# DCDCFinalSchematic.net
KiCad netlist of a schematic drawn in EAGLE
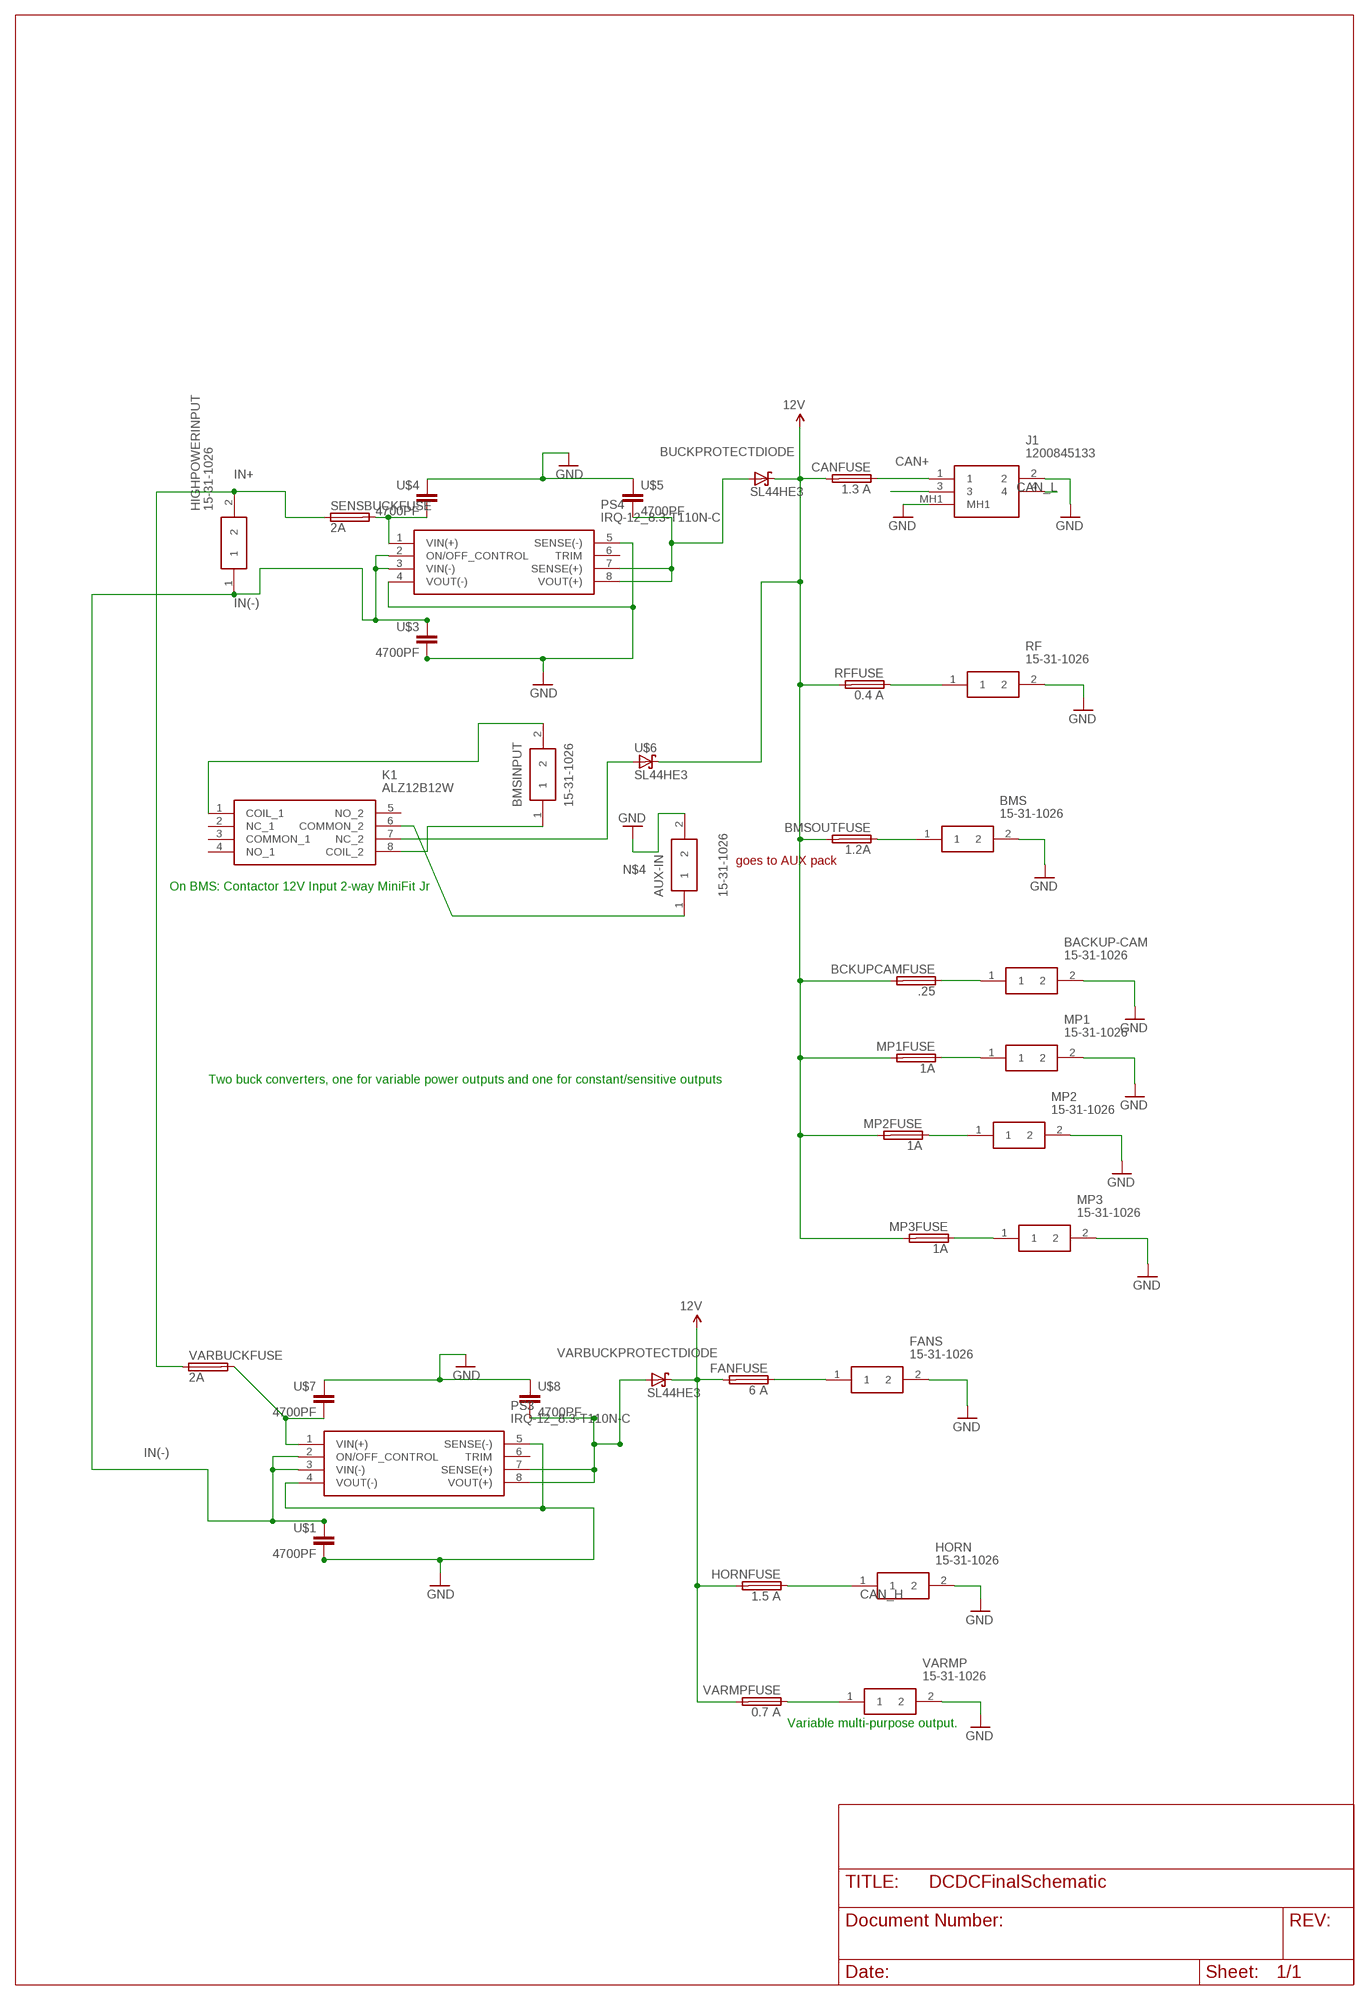
[diagram p0: schematic, sheet 1]

(export (version "E")
  (design (tool "Eeschema 10.0.6"))
  (components
    (comp (ref "AUX-IN")
      (value "15-31-1026")
      (footprint "eagle-import:15311026")
      (fields (field (name "MOUSER_PART_NUMBER") "538-15-31-1026"))
      (libsource (lib "eagle-import") (part "15-31-1026"))
    )
    (comp (ref "BACKUP-CAM")
      (value "15-31-1026")
      (footprint "eagle-import:15311026")
      (fields (field (name "MOUSER_PART_NUMBER") "538-15-31-1026"))
      (libsource (lib "eagle-import") (part "15-31-1026"))
    )
    (comp (ref "BCKUPCAMFUSE")
      (value ".25")
      (footprint "eagle-import:OMNIBLOK")
      (libsource (lib "eagle-import") (part "SMD-MICRO-FUSE-BLOCK"))
    )
    (comp (ref "BMS")
      (value "15-31-1026")
      (footprint "eagle-import:15311026")
      (fields (field (name "MOUSER_PART_NUMBER") "538-15-31-1026"))
      (libsource (lib "eagle-import") (part "15-31-1026"))
    )
    (comp (ref "BMSINPUT")
      (value "15-31-1026")
      (footprint "eagle-import:15311026")
      (fields (field (name "MOUSER_PART_NUMBER") "538-15-31-1026"))
      (libsource (lib "eagle-import") (part "15-31-1026"))
    )
    (comp (ref "BMSOUTFUSE")
      (value "1.2A")
      (footprint "eagle-import:OMNIBLOK")
      (libsource (lib "eagle-import") (part "SMD-MICRO-FUSE-BLOCK"))
    )
    (comp (ref "BUCKPROTECTDIODE")
      (value "SL44HE3")
      (footprint "eagle-import:SMC")
      (libsource (lib "eagle-import") (part "SL44HE3"))
    )
    (comp (ref "CANFUSE")
      (value "1.3 A")
      (footprint "eagle-import:OMNIBLOK")
      (libsource (lib "eagle-import") (part "SMD-MICRO-FUSE-BLOCK"))
    )
    (comp (ref "FANFUSE")
      (value "6 A")
      (footprint "eagle-import:OMNIBLOK")
      (libsource (lib "eagle-import") (part "SMD-MICRO-FUSE-BLOCK"))
    )
    (comp (ref "FANS")
      (value "15-31-1026")
      (footprint "eagle-import:15311026")
      (fields (field (name "MOUSER_PART_NUMBER") "538-15-31-1026"))
      (libsource (lib "eagle-import") (part "15-31-1026"))
    )
    (comp (ref "HIGHPOWERINPUT")
      (value "15-31-1026")
      (footprint "eagle-import:15311026")
      (fields (field (name "MOUSER_PART_NUMBER") "538-15-31-1026"))
      (libsource (lib "eagle-import") (part "15-31-1026"))
    )
    (comp (ref "HORN")
      (value "15-31-1026")
      (footprint "eagle-import:15311026")
      (fields (field (name "MOUSER_PART_NUMBER") "538-15-31-1026"))
      (libsource (lib "eagle-import") (part "15-31-1026"))
    )
    (comp (ref "HORNFUSE")
      (value "1.5 A")
      (footprint "eagle-import:OMNIBLOK")
      (libsource (lib "eagle-import") (part "SMD-MICRO-FUSE-BLOCK"))
    )
    (comp (ref "J1")
      (value "1200845133")
      (footprint "eagle-import:1200845133")
      (fields (field (name "MOUSER_PART_NUMBER") "538-1200845133"))
      (libsource (lib "eagle-import") (part "1200845133"))
    )
    (comp (ref "K1")
      (value "ALZ12B12W")
      (footprint "eagle-import:ALZ12B12W")
      (libsource (lib "eagle-import") (part "ALZ12B12W"))
    )
    (comp (ref "MP1")
      (value "15-31-1026")
      (footprint "eagle-import:15311026")
      (fields (field (name "MOUSER_PART_NUMBER") "538-15-31-1026"))
      (libsource (lib "eagle-import") (part "15-31-1026"))
    )
    (comp (ref "MP1FUSE")
      (value "1A")
      (footprint "eagle-import:OMNIBLOK")
      (libsource (lib "eagle-import") (part "SMD-MICRO-FUSE-BLOCK"))
    )
    (comp (ref "MP2")
      (value "15-31-1026")
      (footprint "eagle-import:15311026")
      (fields (field (name "MOUSER_PART_NUMBER") "538-15-31-1026"))
      (libsource (lib "eagle-import") (part "15-31-1026"))
    )
    (comp (ref "MP2FUSE")
      (value "1A")
      (footprint "eagle-import:OMNIBLOK")
      (libsource (lib "eagle-import") (part "SMD-MICRO-FUSE-BLOCK"))
    )
    (comp (ref "MP3")
      (value "15-31-1026")
      (footprint "eagle-import:15311026")
      (fields (field (name "MOUSER_PART_NUMBER") "538-15-31-1026"))
      (libsource (lib "eagle-import") (part "15-31-1026"))
    )
    (comp (ref "MP3FUSE")
      (value "1A")
      (footprint "eagle-import:OMNIBLOK")
      (libsource (lib "eagle-import") (part "SMD-MICRO-FUSE-BLOCK"))
    )
    (comp (ref "PS3")
      (value "IRQ-12_8.3-T110N-C")
      (footprint "eagle-import:IRQ1283T110NC")
      (fields
        (field (name "MANUFACTURER_PART_NUMBER") "IRQ-12/8.3-T110N-C")
        (field (name "MOUSER_PART_NUMBER") "580-IRQ-12/8.3T110NC")
      )
      (libsource (lib "eagle-import") (part "IRQ-12_8.3-T110N-C"))
    )
    (comp (ref "PS4")
      (value "IRQ-12_8.3-T110N-C")
      (footprint "eagle-import:IRQ1283T110NC")
      (fields
        (field (name "MANUFACTURER_PART_NUMBER") "IRQ-12/8.3-T110N-C")
        (field (name "MOUSER_PART_NUMBER") "580-IRQ-12/8.3T110NC")
      )
      (libsource (lib "eagle-import") (part "IRQ-12_8.3-T110N-C"))
    )
    (comp (ref "RF")
      (value "15-31-1026")
      (footprint "eagle-import:15311026")
      (fields (field (name "MOUSER_PART_NUMBER") "538-15-31-1026"))
      (libsource (lib "eagle-import") (part "15-31-1026"))
    )
    (comp (ref "RFFUSE")
      (value "0.4 A")
      (footprint "eagle-import:OMNIBLOK")
      (libsource (lib "eagle-import") (part "SMD-MICRO-FUSE-BLOCK"))
    )
    (comp (ref "SENSBUCKFUSE")
      (value "2A")
      (footprint "eagle-import:OMNIBLOK")
      (libsource (lib "eagle-import") (part "SMD-MICRO-FUSE-BLOCK"))
    )
    (comp (ref "U$1")
      (value "4700PF")
      (footprint "eagle-import:Y2_CAP")
      (libsource (lib "eagle-import") (part "4700PF"))
    )
    (comp (ref "U$3")
      (value "4700PF")
      (footprint "eagle-import:Y2_CAP")
      (libsource (lib "eagle-import") (part "4700PF"))
    )
    (comp (ref "U$4")
      (value "4700PF")
      (footprint "eagle-import:Y2_CAP")
      (libsource (lib "eagle-import") (part "4700PF"))
    )
    (comp (ref "U$5")
      (value "4700PF")
      (footprint "eagle-import:Y2_CAP")
      (libsource (lib "eagle-import") (part "4700PF"))
    )
    (comp (ref "U$6")
      (value "SL44HE3")
      (footprint "eagle-import:SMC")
      (libsource (lib "eagle-import") (part "SL44HE3"))
    )
    (comp (ref "U$7")
      (value "4700PF")
      (footprint "eagle-import:Y2_CAP")
      (libsource (lib "eagle-import") (part "4700PF"))
    )
    (comp (ref "U$8")
      (value "4700PF")
      (footprint "eagle-import:Y2_CAP")
      (libsource (lib "eagle-import") (part "4700PF"))
    )
    (comp (ref "VARBUCKFUSE")
      (value "2A")
      (footprint "eagle-import:OMNIBLOK")
      (libsource (lib "eagle-import") (part "SMD-MICRO-FUSE-BLOCK"))
    )
    (comp (ref "VARBUCKPROTECTDIODE")
      (value "SL44HE3")
      (footprint "eagle-import:SMC")
      (libsource (lib "eagle-import") (part "SL44HE3"))
    )
    (comp (ref "VARMP")
      (value "15-31-1026")
      (footprint "eagle-import:15311026")
      (fields (field (name "MOUSER_PART_NUMBER") "538-15-31-1026"))
      (libsource (lib "eagle-import") (part "15-31-1026"))
    )
    (comp (ref "VARMPFUSE")
      (value "0.7 A")
      (footprint "eagle-import:OMNIBLOK")
      (libsource (lib "eagle-import") (part "SMD-MICRO-FUSE-BLOCK"))
    )
  )
  (nets
    (net (code "1") (name "/CAN+") (class "Default")
      (node (ref "BACKUP-CAM") (pin "1") (pinfunction "1_1") (pintype "bidirectional"))
      (node (ref "BCKUPCAMFUSE") (pin "P$1") (pinfunction "1_P$1") (pintype "passive"))
      (node (ref "CANFUSE") (pin "P$1") (pinfunction "1_P$1") (pintype "passive"))
      (node (ref "J1") (pin "1") (pinfunction "1_1") (pintype "bidirectional"))
    )
    (net (code "2") (name "/CAN_H") (class "Default")
      (node (ref "J1") (pin "3") (pinfunction "3_3") (pintype "bidirectional"))
    )
    (net (code "3") (name "/CAN_L") (class "Default")
      (node (ref "J1") (pin "4") (pinfunction "4_4") (pintype "bidirectional"))
    )
    (net (code "4") (name "/IN(-)") (class "Default")
      (node (ref "HIGHPOWERINPUT") (pin "1") (pinfunction "1_1") (pintype "bidirectional"))
      (node (ref "PS3") (pin "2") (pinfunction "ON/OFF_CONTROL_2") (pintype "bidirectional"))
      (node (ref "PS3") (pin "3") (pinfunction "VIN(-)_3") (pintype "bidirectional"))
      (node (ref "PS4") (pin "2") (pinfunction "ON/OFF_CONTROL_2") (pintype "bidirectional"))
      (node (ref "PS4") (pin "3") (pinfunction "VIN(-)_3") (pintype "bidirectional"))
      (node (ref "U$1") (pin "P$1") (pinfunction "1_P$1") (pintype "passive"))
      (node (ref "U$3") (pin "P$1") (pinfunction "1_P$1") (pintype "passive"))
    )
    (net (code "5") (name "/IN+") (class "Default")
      (node (ref "HIGHPOWERINPUT") (pin "2") (pinfunction "2_2") (pintype "bidirectional"))
      (node (ref "SENSBUCKFUSE") (pin "P$1") (pinfunction "1_P$1") (pintype "passive"))
      (node (ref "VARBUCKFUSE") (pin "P$1") (pinfunction "1_P$1") (pintype "passive"))
    )
    (net (code "6") (name "/N$4") (class "Default")
      (node (ref "BMSINPUT") (pin "2") (pinfunction "2_2") (pintype "bidirectional"))
      (node (ref "K1") (pin "1") (pinfunction "COIL_1_1") (pintype "bidirectional"))
      (node (ref "K1") (pin "7") (pinfunction "NC_2_7") (pintype "bidirectional"))
      (node (ref "U$6") (pin "A") (pinfunction "A_A") (pintype "passive"))
    )
    (net (code "7") (name "12V") (class "Default")
      (node (ref "BCKUPCAMFUSE") (pin "P$2") (pinfunction "2_P$2") (pintype "passive"))
      (node (ref "BMSOUTFUSE") (pin "P$2") (pinfunction "2_P$2") (pintype "passive"))
      (node (ref "BUCKPROTECTDIODE") (pin "C") (pinfunction "C_C") (pintype "passive"))
      (node (ref "CANFUSE") (pin "P$2") (pinfunction "2_P$2") (pintype "passive"))
      (node (ref "FANFUSE") (pin "P$2") (pinfunction "2_P$2") (pintype "passive"))
      (node (ref "HORNFUSE") (pin "P$2") (pinfunction "2_P$2") (pintype "passive"))
      (node (ref "MP1FUSE") (pin "P$2") (pinfunction "2_P$2") (pintype "passive"))
      (node (ref "MP2FUSE") (pin "P$2") (pinfunction "2_P$2") (pintype "passive"))
      (node (ref "MP3FUSE") (pin "P$2") (pinfunction "2_P$2") (pintype "passive"))
      (node (ref "RFFUSE") (pin "P$2") (pinfunction "2_P$2") (pintype "passive"))
      (node (ref "U$6") (pin "C") (pinfunction "C_C") (pintype "passive"))
      (node (ref "VARBUCKPROTECTDIODE") (pin "C") (pinfunction "C_C") (pintype "passive"))
      (node (ref "VARMPFUSE") (pin "P$2") (pinfunction "2_P$2") (pintype "passive"))
    )
    (net (code "8") (name "GND") (class "Default")
      (node (ref "AUX-IN") (pin "2") (pinfunction "2_2") (pintype "bidirectional"))
      (node (ref "BACKUP-CAM") (pin "2") (pinfunction "2_2") (pintype "bidirectional"))
      (node (ref "BMS") (pin "2") (pinfunction "2_2") (pintype "bidirectional"))
      (node (ref "FANS") (pin "2") (pinfunction "2_2") (pintype "bidirectional"))
      (node (ref "HORN") (pin "2") (pinfunction "2_2") (pintype "bidirectional"))
      (node (ref "J1") (pin "2") (pinfunction "2_2") (pintype "bidirectional"))
      (node (ref "J1") (pin "MH1") (pinfunction "MH1_MH1") (pintype "bidirectional"))
      (node (ref "MP1") (pin "2") (pinfunction "2_2") (pintype "bidirectional"))
      (node (ref "MP2") (pin "2") (pinfunction "2_2") (pintype "bidirectional"))
      (node (ref "MP3") (pin "2") (pinfunction "2_2") (pintype "bidirectional"))
      (node (ref "PS3") (pin "4") (pinfunction "VOUT(-)_4") (pintype "bidirectional"))
      (node (ref "PS3") (pin "5") (pinfunction "SENSE(-)_5") (pintype "bidirectional"))
      (node (ref "PS4") (pin "4") (pinfunction "VOUT(-)_4") (pintype "bidirectional"))
      (node (ref "PS4") (pin "5") (pinfunction "SENSE(-)_5") (pintype "bidirectional"))
      (node (ref "RF") (pin "2") (pinfunction "2_2") (pintype "bidirectional"))
      (node (ref "U$1") (pin "P$2") (pinfunction "2_P$2") (pintype "passive"))
      (node (ref "U$3") (pin "P$2") (pinfunction "2_P$2") (pintype "passive"))
      (node (ref "U$4") (pin "P$1") (pinfunction "1_P$1") (pintype "passive"))
      (node (ref "U$5") (pin "P$1") (pinfunction "1_P$1") (pintype "passive"))
      (node (ref "U$7") (pin "P$1") (pinfunction "1_P$1") (pintype "passive"))
      (node (ref "U$8") (pin "P$1") (pinfunction "1_P$1") (pintype "passive"))
      (node (ref "VARMP") (pin "2") (pinfunction "2_2") (pintype "bidirectional"))
    )
    (net (code "9") (name "Net-(BMSOUTFUSE-1)") (class "Default")
      (node (ref "BMS") (pin "1") (pinfunction "1_1") (pintype "bidirectional"))
      (node (ref "BMSOUTFUSE") (pin "P$1") (pinfunction "1_P$1") (pintype "passive"))
    )
    (net (code "10") (name "Net-(FANFUSE-1)") (class "Default")
      (node (ref "FANFUSE") (pin "P$1") (pinfunction "1_P$1") (pintype "passive"))
      (node (ref "FANS") (pin "1") (pinfunction "1_1") (pintype "bidirectional"))
    )
    (net (code "11") (name "Net-(HORNFUSE-1)") (class "Default")
      (node (ref "HORN") (pin "1") (pinfunction "1_1") (pintype "bidirectional"))
      (node (ref "HORNFUSE") (pin "P$1") (pinfunction "1_P$1") (pintype "passive"))
    )
    (net (code "12") (name "Net-(K1-COIL_2)") (class "Default")
      (node (ref "BMSINPUT") (pin "1") (pinfunction "1_1") (pintype "bidirectional"))
      (node (ref "K1") (pin "8") (pinfunction "COIL_2_8") (pintype "bidirectional"))
    )
    (net (code "13") (name "Net-(K1-COMMON_2)") (class "Default")
      (node (ref "AUX-IN") (pin "1") (pinfunction "1_1") (pintype "bidirectional"))
      (node (ref "K1") (pin "6") (pinfunction "COMMON_2_6") (pintype "bidirectional"))
    )
    (net (code "14") (name "Net-(MP1FUSE-1)") (class "Default")
      (node (ref "MP1") (pin "1") (pinfunction "1_1") (pintype "bidirectional"))
      (node (ref "MP1FUSE") (pin "P$1") (pinfunction "1_P$1") (pintype "passive"))
    )
    (net (code "15") (name "Net-(MP2FUSE-1)") (class "Default")
      (node (ref "MP2") (pin "1") (pinfunction "1_1") (pintype "bidirectional"))
      (node (ref "MP2FUSE") (pin "P$1") (pinfunction "1_P$1") (pintype "passive"))
    )
    (net (code "16") (name "Net-(MP3FUSE-1)") (class "Default")
      (node (ref "MP3") (pin "1") (pinfunction "1_1") (pintype "bidirectional"))
      (node (ref "MP3FUSE") (pin "P$1") (pinfunction "1_P$1") (pintype "passive"))
    )
    (net (code "17") (name "Net-(PS3-SENSE(+))") (class "Default")
      (node (ref "PS3") (pin "7") (pinfunction "SENSE(+)_7") (pintype "bidirectional"))
      (node (ref "PS3") (pin "8") (pinfunction "VOUT(+)_8") (pintype "bidirectional"))
      (node (ref "U$8") (pin "P$2") (pinfunction "2_P$2") (pintype "passive"))
      (node (ref "VARBUCKPROTECTDIODE") (pin "A") (pinfunction "A_A") (pintype "passive"))
    )
    (net (code "18") (name "Net-(PS3-VIN(+))") (class "Default")
      (node (ref "PS3") (pin "1") (pinfunction "VIN(+)_1") (pintype "bidirectional"))
      (node (ref "U$7") (pin "P$2") (pinfunction "2_P$2") (pintype "passive"))
      (node (ref "VARBUCKFUSE") (pin "P$2") (pinfunction "2_P$2") (pintype "passive"))
    )
    (net (code "19") (name "Net-(PS4-SENSE(+))") (class "Default")
      (node (ref "BUCKPROTECTDIODE") (pin "A") (pinfunction "A_A") (pintype "passive"))
      (node (ref "PS4") (pin "7") (pinfunction "SENSE(+)_7") (pintype "bidirectional"))
      (node (ref "PS4") (pin "8") (pinfunction "VOUT(+)_8") (pintype "bidirectional"))
      (node (ref "U$5") (pin "P$2") (pinfunction "2_P$2") (pintype "passive"))
    )
    (net (code "20") (name "Net-(PS4-VIN(+))") (class "Default")
      (node (ref "PS4") (pin "1") (pinfunction "VIN(+)_1") (pintype "bidirectional"))
      (node (ref "SENSBUCKFUSE") (pin "P$2") (pinfunction "2_P$2") (pintype "passive"))
      (node (ref "U$4") (pin "P$2") (pinfunction "2_P$2") (pintype "passive"))
    )
    (net (code "21") (name "Net-(RFFUSE-1)") (class "Default")
      (node (ref "RF") (pin "1") (pinfunction "1_1") (pintype "bidirectional"))
      (node (ref "RFFUSE") (pin "P$1") (pinfunction "1_P$1") (pintype "passive"))
    )
    (net (code "22") (name "Net-(VARMPFUSE-1)") (class "Default")
      (node (ref "VARMP") (pin "1") (pinfunction "1_1") (pintype "bidirectional"))
      (node (ref "VARMPFUSE") (pin "P$1") (pinfunction "1_P$1") (pintype "passive"))
    )
    (net (code "23") (name "unconnected-(K1-COMMON_1-Pad3)") (class "Default")
      (node (ref "K1") (pin "3") (pinfunction "COMMON_1_3") (pintype "bidirectional"))
    )
    (net (code "24") (name "unconnected-(K1-NC_1-Pad2)") (class "Default")
      (node (ref "K1") (pin "2") (pinfunction "NC_1_2") (pintype "bidirectional"))
    )
    (net (code "25") (name "unconnected-(K1-NO_1-Pad4)") (class "Default")
      (node (ref "K1") (pin "4") (pinfunction "NO_1_4") (pintype "bidirectional"))
    )
    (net (code "26") (name "unconnected-(K1-NO_2-Pad5)") (class "Default")
      (node (ref "K1") (pin "5") (pinfunction "NO_2_5") (pintype "bidirectional"))
    )
    (net (code "27") (name "unconnected-(PS3-TRIM-Pad6)") (class "Default")
      (node (ref "PS3") (pin "6") (pinfunction "TRIM_6") (pintype "bidirectional"))
    )
    (net (code "28") (name "unconnected-(PS4-TRIM-Pad6)") (class "Default")
      (node (ref "PS4") (pin "6") (pinfunction "TRIM_6") (pintype "bidirectional"))
    )
  )
)
